# CC2530.net
KiCad netlist of a schematic drawn in EAGLE
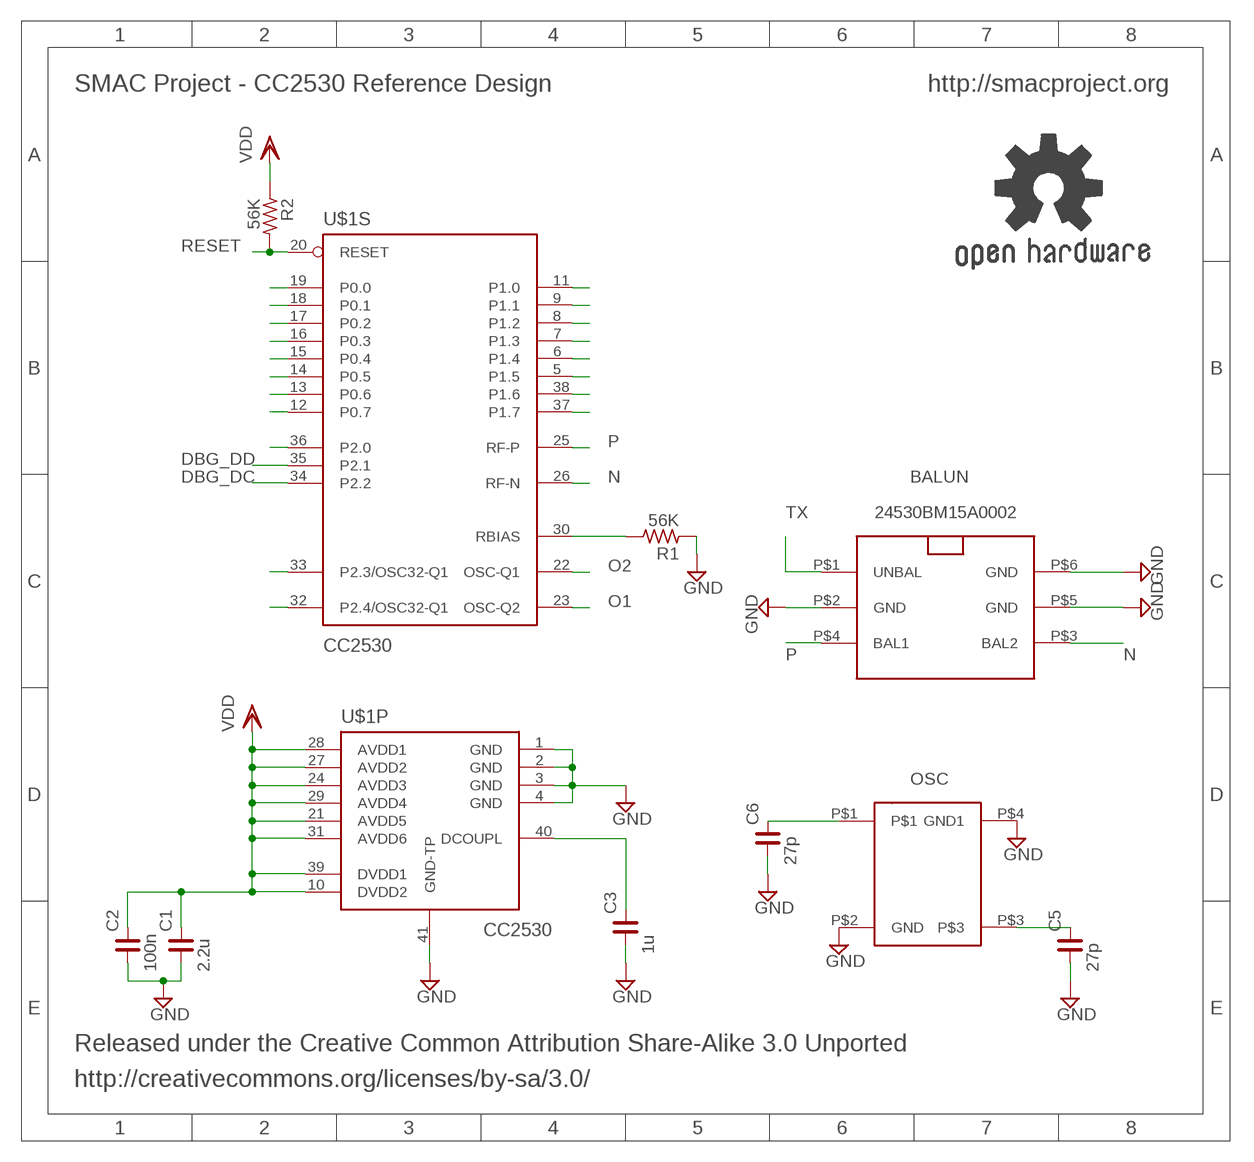
[diagram p0: schematic, sheet 1]

(export (version "E")
  (design (tool "Eeschema 10.0.6"))
  (components
    (comp (ref "C1")
      (value "2.2u")
      (footprint "eagle-import:C0402")
      (libsource (lib "eagle-import") (part "C_0402"))
    )
    (comp (ref "C2")
      (value "100n")
      (footprint "eagle-import:C0402")
      (libsource (lib "eagle-import") (part "C_0402"))
    )
    (comp (ref "C3")
      (value "1u")
      (footprint "eagle-import:C0402")
      (libsource (lib "eagle-import") (part "C_0402"))
    )
    (comp (ref "C5")
      (value "27p")
      (footprint "eagle-import:C0402")
      (libsource (lib "eagle-import") (part "C_0402"))
    )
    (comp (ref "C6")
      (value "27p")
      (footprint "eagle-import:C0402")
      (libsource (lib "eagle-import") (part "C_0402"))
    )
    (comp (ref "GOLD_ORB_SM2")
      (value "OSHWLOGO_REF_SM")
      (footprint "eagle-import:OSHW2REF")
      (libsource (lib "eagle-import") (part "OSHWLOGO_REF_SM"))
    )
    (comp (ref "R1")
      (value "56K")
      (footprint "eagle-import:R0402")
      (libsource (lib "eagle-import") (part "R_0402"))
    )
    (comp (ref "R2")
      (value "56K")
      (footprint "eagle-import:R0402")
      (libsource (lib "eagle-import") (part "R_0402"))
    )
    (comp (ref "U$1")
      (value "CC2530")
      (footprint "eagle-import:QFN50P600X600X100-41N")
      (libsource (lib "eagle-import") (part "CC2530"))
    )
    (comp (ref "U$2")
      (value "24530BM15A0002")
      (footprint "eagle-import:24530BM15A0002")
      (libsource (lib "eagle-import") (part "24530BM15A0002"))
    )
    (comp (ref "U$3")
      (value "ABM_10")
      (footprint "eagle-import:ABM_OSC")
      (libsource (lib "eagle-import") (part "ABM_10"))
    )
  )
  (nets
    (net (code "1") (name "/DBG_DC") (class "Default")
      (node (ref "U$1") (pin "34") (pinfunction "P2.2_34") (pintype "bidirectional"))
    )
    (net (code "2") (name "/DBG_DD") (class "Default")
      (node (ref "U$1") (pin "35") (pinfunction "P2.1_35") (pintype "bidirectional"))
    )
    (net (code "3") (name "/N") (class "Default")
      (node (ref "U$1") (pin "26") (pinfunction "RF-N_26") (pintype "bidirectional"))
      (node (ref "U$2") (pin "P$3") (pinfunction "BAL2_P$3") (pintype "bidirectional"))
    )
    (net (code "4") (name "/O1") (class "Default")
      (node (ref "C6") (pin "2") (pinfunction "2_2") (pintype "passive"))
      (node (ref "U$1") (pin "23") (pinfunction "OSC-Q2_23") (pintype "bidirectional"))
      (node (ref "U$3") (pin "P$1") (pinfunction "P$1_P$1") (pintype "bidirectional"))
    )
    (net (code "5") (name "/O2") (class "Default")
      (node (ref "C5") (pin "2") (pinfunction "2_2") (pintype "passive"))
      (node (ref "U$1") (pin "22") (pinfunction "OSC-Q1_22") (pintype "bidirectional"))
      (node (ref "U$3") (pin "P$3") (pinfunction "P$3_P$3") (pintype "bidirectional"))
    )
    (net (code "6") (name "/P") (class "Default")
      (node (ref "U$1") (pin "25") (pinfunction "RF-P_25") (pintype "bidirectional"))
      (node (ref "U$2") (pin "P$4") (pinfunction "BAL1_P$4") (pintype "bidirectional"))
    )
    (net (code "7") (name "/RESET") (class "Default")
      (node (ref "R2") (pin "2") (pinfunction "2_2") (pintype "passive"))
      (node (ref "U$1") (pin "20") (pinfunction "RESET_20") (pintype "input"))
    )
    (net (code "8") (name "/TX") (class "Default")
      (node (ref "U$2") (pin "P$1") (pinfunction "UNBAL_P$1") (pintype "bidirectional"))
    )
    (net (code "9") (name "GND") (class "Default")
      (node (ref "C1") (pin "1") (pinfunction "1_1") (pintype "passive"))
      (node (ref "C2") (pin "1") (pinfunction "1_1") (pintype "passive"))
      (node (ref "C3") (pin "1") (pinfunction "1_1") (pintype "passive"))
      (node (ref "C5") (pin "1") (pinfunction "1_1") (pintype "passive"))
      (node (ref "C6") (pin "1") (pinfunction "1_1") (pintype "passive"))
      (node (ref "R1") (pin "1") (pinfunction "1_1") (pintype "passive"))
      (node (ref "U$1") (pin "1") (pinfunction "GND_1") (pintype "power_in"))
      (node (ref "U$1") (pin "2") (pinfunction "GND_2") (pintype "power_in"))
      (node (ref "U$1") (pin "3") (pinfunction "GND_3") (pintype "power_in"))
      (node (ref "U$1") (pin "4") (pinfunction "GND_4") (pintype "power_in"))
      (node (ref "U$1") (pin "41") (pinfunction "GND-TP_41") (pintype "power_in"))
      (node (ref "U$2") (pin "P$2") (pinfunction "GND_P$2") (pintype "power_in"))
      (node (ref "U$2") (pin "P$5") (pinfunction "GND_P$5") (pintype "power_in"))
      (node (ref "U$2") (pin "P$6") (pinfunction "GND_P$6") (pintype "power_in"))
      (node (ref "U$3") (pin "P$2") (pinfunction "GND_P$2") (pintype "bidirectional"))
      (node (ref "U$3") (pin "P$4") (pinfunction "GND1_P$4") (pintype "bidirectional"))
    )
    (net (code "10") (name "Net-(U$1A-DCOUPL)") (class "Default")
      (node (ref "C3") (pin "2") (pinfunction "2_2") (pintype "passive"))
      (node (ref "U$1") (pin "40") (pinfunction "DCOUPL_40") (pintype "power_in"))
    )
    (net (code "11") (name "Net-(U$1B-RBIAS)") (class "Default")
      (node (ref "R1") (pin "2") (pinfunction "2_2") (pintype "passive"))
      (node (ref "U$1") (pin "30") (pinfunction "RBIAS_30") (pintype "bidirectional"))
    )
    (net (code "12") (name "VDD") (class "Default")
      (node (ref "C1") (pin "2") (pinfunction "2_2") (pintype "passive"))
      (node (ref "C2") (pin "2") (pinfunction "2_2") (pintype "passive"))
      (node (ref "R2") (pin "1") (pinfunction "1_1") (pintype "passive"))
      (node (ref "U$1") (pin "10") (pinfunction "DVDD2_10") (pintype "power_in"))
      (node (ref "U$1") (pin "21") (pinfunction "AVDD5_21") (pintype "power_in"))
      (node (ref "U$1") (pin "24") (pinfunction "AVDD3_24") (pintype "power_in"))
      (node (ref "U$1") (pin "27") (pinfunction "AVDD2_27") (pintype "power_in"))
      (node (ref "U$1") (pin "28") (pinfunction "AVDD1_28") (pintype "power_in"))
      (node (ref "U$1") (pin "29") (pinfunction "AVDD4_29") (pintype "power_in"))
      (node (ref "U$1") (pin "31") (pinfunction "AVDD6_31") (pintype "power_in"))
      (node (ref "U$1") (pin "39") (pinfunction "DVDD1_39") (pintype "power_in"))
    )
    (net (code "13") (name "unconnected-(U$1B-P0.0-Pad19)") (class "Default")
      (node (ref "U$1") (pin "19") (pinfunction "P0.0_19") (pintype "bidirectional"))
    )
    (net (code "14") (name "unconnected-(U$1B-P0.1-Pad18)") (class "Default")
      (node (ref "U$1") (pin "18") (pinfunction "P0.1_18") (pintype "bidirectional"))
    )
    (net (code "15") (name "unconnected-(U$1B-P0.2-Pad17)") (class "Default")
      (node (ref "U$1") (pin "17") (pinfunction "P0.2_17") (pintype "bidirectional"))
    )
    (net (code "16") (name "unconnected-(U$1B-P0.3-Pad16)") (class "Default")
      (node (ref "U$1") (pin "16") (pinfunction "P0.3_16") (pintype "bidirectional"))
    )
    (net (code "17") (name "unconnected-(U$1B-P0.4-Pad15)") (class "Default")
      (node (ref "U$1") (pin "15") (pinfunction "P0.4_15") (pintype "bidirectional"))
    )
    (net (code "18") (name "unconnected-(U$1B-P0.5-Pad14)") (class "Default")
      (node (ref "U$1") (pin "14") (pinfunction "P0.5_14") (pintype "bidirectional"))
    )
    (net (code "19") (name "unconnected-(U$1B-P0.6-Pad13)") (class "Default")
      (node (ref "U$1") (pin "13") (pinfunction "P0.6_13") (pintype "bidirectional"))
    )
    (net (code "20") (name "unconnected-(U$1B-P0.7-Pad12)") (class "Default")
      (node (ref "U$1") (pin "12") (pinfunction "P0.7_12") (pintype "bidirectional"))
    )
    (net (code "21") (name "unconnected-(U$1B-P1.0-Pad11)") (class "Default")
      (node (ref "U$1") (pin "11") (pinfunction "P1.0_11") (pintype "bidirectional"))
    )
    (net (code "22") (name "unconnected-(U$1B-P1.1-Pad9)") (class "Default")
      (node (ref "U$1") (pin "9") (pinfunction "P1.1_9") (pintype "bidirectional"))
    )
    (net (code "23") (name "unconnected-(U$1B-P1.2-Pad8)") (class "Default")
      (node (ref "U$1") (pin "8") (pinfunction "P1.2_8") (pintype "bidirectional"))
    )
    (net (code "24") (name "unconnected-(U$1B-P1.3-Pad7)") (class "Default")
      (node (ref "U$1") (pin "7") (pinfunction "P1.3_7") (pintype "bidirectional"))
    )
    (net (code "25") (name "unconnected-(U$1B-P1.4-Pad6)") (class "Default")
      (node (ref "U$1") (pin "6") (pinfunction "P1.4_6") (pintype "bidirectional"))
    )
    (net (code "26") (name "unconnected-(U$1B-P1.5-Pad5)") (class "Default")
      (node (ref "U$1") (pin "5") (pinfunction "P1.5_5") (pintype "bidirectional"))
    )
    (net (code "27") (name "unconnected-(U$1B-P1.6-Pad38)") (class "Default")
      (node (ref "U$1") (pin "38") (pinfunction "P1.6_38") (pintype "bidirectional"))
    )
    (net (code "28") (name "unconnected-(U$1B-P1.7-Pad37)") (class "Default")
      (node (ref "U$1") (pin "37") (pinfunction "P1.7_37") (pintype "bidirectional"))
    )
    (net (code "29") (name "unconnected-(U$1B-P2.0-Pad36)") (class "Default")
      (node (ref "U$1") (pin "36") (pinfunction "P2.0_36") (pintype "bidirectional"))
    )
    (net (code "30") (name "unconnected-(U$1B-P2.3{slash}OSC32-Q1-Pad33)") (class "Default")
      (node (ref "U$1") (pin "33") (pinfunction "P2.3/OSC32-Q1_33") (pintype "bidirectional"))
    )
    (net (code "31") (name "unconnected-(U$1B-P2.4{slash}OSC32-Q1-Pad32)") (class "Default")
      (node (ref "U$1") (pin "32") (pinfunction "P2.4/OSC32-Q1_32") (pintype "bidirectional"))
    )
  )
)
